# V1_0.net
KiCad netlist of a schematic drawn in Altium Designer
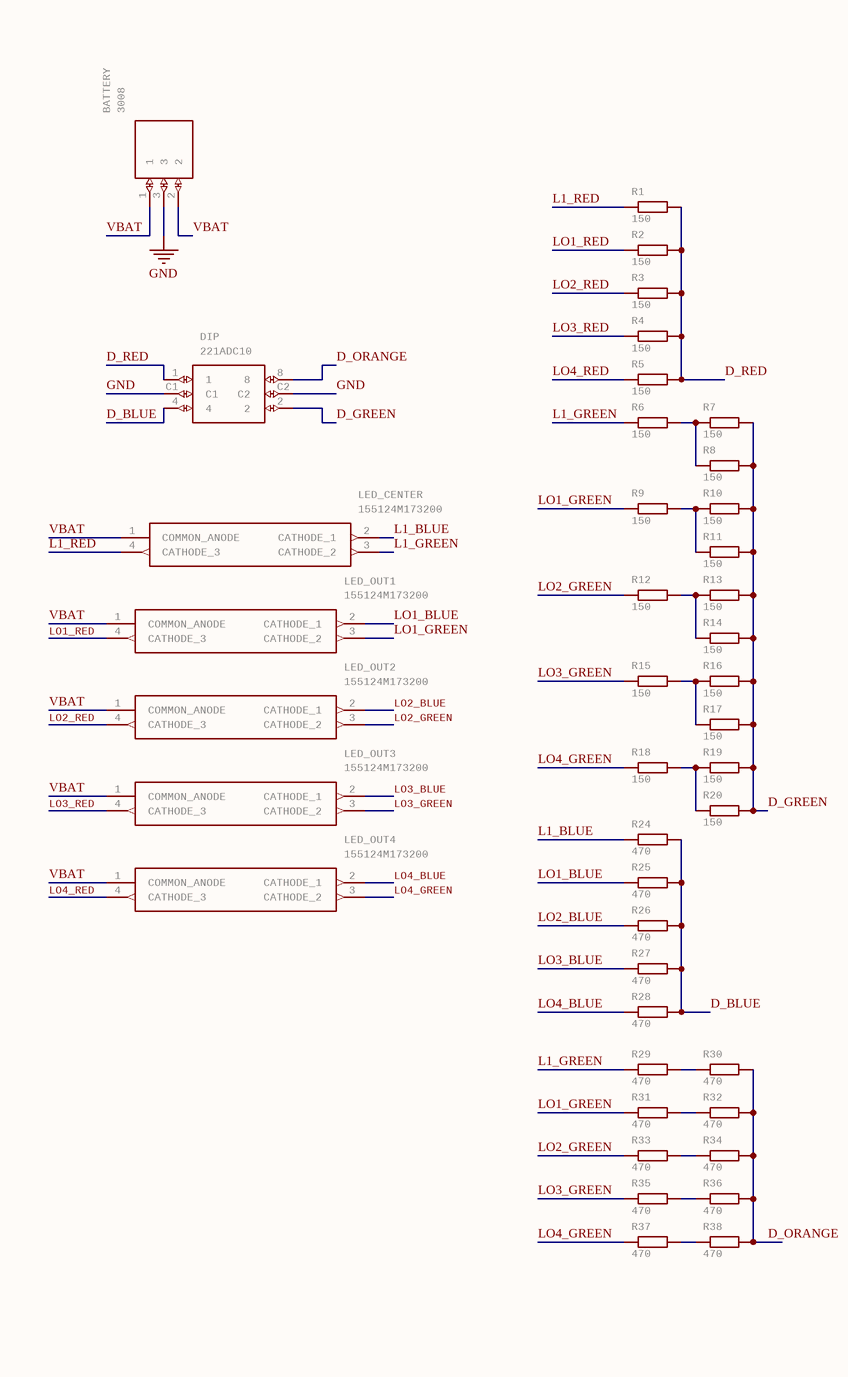
[diagram p0: V1.0.SchDoc]

(export (version "E")
  (design (tool "Eeschema 10.0.6"))
  (components
    (comp (ref "BATTERY")
      (value "3008")
      (footprint "3008")
      (description "BATTERY SOCKET   Source:  Datasheet")
      (fields (field (name "MOUSER_PART_NUMBER") "534-3008"))
      (libsource (lib "SamacSys_Parts") (part "3008"))
    )
    (comp (ref "DIP")
      (value "221ADC10")
      (footprint "221ADC10")
      (description "SWITCH ROTARY DIP BCD 100MA 50V   Source:  Datasheet")
      (fields (field (name "RS_PART_NUMBER") "1234573"))
      (libsource (lib "SamacSys_Parts") (part "221ADC10"))
    )
    (comp (ref "LED_CENTER")
      (value "155124M173200")
      (footprint "155124M173200")
      (description "WURTH ELEKTRONIK - 155124M173200 - LED, RED/GRN/BLUE, 450/850/140MCD, 1204   Source:  Datasheet")
      (fields
        (field (name "ARROW_PART_NUMBER") "ARROW_PART_NUMBER")
        (field (name "MOUSER_PART_NUMBER") "710-155124M173200")
      )
      (libsource (lib "SamacSys_Parts") (part "155124M173200"))
    )
    (comp (ref "LED_OUT1")
      (value "155124M173200")
      (footprint "155124M173200")
      (description "WURTH ELEKTRONIK - 155124M173200 - LED, RED/GRN/BLUE, 450/850/140MCD, 1204   Source:  Datasheet")
      (fields
        (field (name "ARROW_PART_NUMBER") "ARROW_PART_NUMBER")
        (field (name "MOUSER_PART_NUMBER") "710-155124M173200")
      )
      (libsource (lib "SamacSys_Parts") (part "155124M173200"))
    )
    (comp (ref "LED_OUT2")
      (value "155124M173200")
      (footprint "155124M173200")
      (description "WURTH ELEKTRONIK - 155124M173200 - LED, RED/GRN/BLUE, 450/850/140MCD, 1204   Source:  Datasheet")
      (fields
        (field (name "ARROW_PART_NUMBER") "ARROW_PART_NUMBER")
        (field (name "MOUSER_PART_NUMBER") "710-155124M173200")
      )
      (libsource (lib "SamacSys_Parts") (part "155124M173200"))
    )
    (comp (ref "LED_OUT3")
      (value "155124M173200")
      (footprint "155124M173200")
      (description "WURTH ELEKTRONIK - 155124M173200 - LED, RED/GRN/BLUE, 450/850/140MCD, 1204   Source:  Datasheet")
      (fields
        (field (name "ARROW_PART_NUMBER") "ARROW_PART_NUMBER")
        (field (name "MOUSER_PART_NUMBER") "710-155124M173200")
      )
      (libsource (lib "SamacSys_Parts") (part "155124M173200"))
    )
    (comp (ref "LED_OUT4")
      (value "155124M173200")
      (footprint "155124M173200")
      (description "WURTH ELEKTRONIK - 155124M173200 - LED, RED/GRN/BLUE, 450/850/140MCD, 1204   Source:  Datasheet")
      (fields
        (field (name "ARROW_PART_NUMBER") "ARROW_PART_NUMBER")
        (field (name "MOUSER_PART_NUMBER") "710-155124M173200")
      )
      (libsource (lib "SamacSys_Parts") (part "155124M173200"))
    )
    (comp (ref "R1")
      (value "150")
      (footprint "R0603")
      (description "RESISTOR, European symbol")
      (libsource (lib "rcl") (part "R-EU_R0603"))
    )
    (comp (ref "R2")
      (value "150")
      (footprint "R0603")
      (description "RESISTOR, European symbol")
      (libsource (lib "rcl") (part "R-EU_R0603"))
    )
    (comp (ref "R3")
      (value "150")
      (footprint "R0603")
      (description "RESISTOR, European symbol")
      (libsource (lib "rcl") (part "R-EU_R0603"))
    )
    (comp (ref "R4")
      (value "150")
      (footprint "R0603")
      (description "RESISTOR, European symbol")
      (libsource (lib "rcl") (part "R-EU_R0603"))
    )
    (comp (ref "R5")
      (value "150")
      (footprint "R0603")
      (description "RESISTOR, European symbol")
      (libsource (lib "rcl") (part "R-EU_R0603"))
    )
    (comp (ref "R6")
      (value "150")
      (footprint "R0603")
      (description "RESISTOR, European symbol")
      (libsource (lib "rcl") (part "R-EU_R0603"))
    )
    (comp (ref "R7")
      (value "150")
      (footprint "R0603")
      (description "RESISTOR, European symbol")
      (libsource (lib "rcl") (part "R-EU_R0603"))
    )
    (comp (ref "R8")
      (value "150")
      (footprint "R0603")
      (description "RESISTOR, European symbol")
      (libsource (lib "rcl") (part "R-EU_R0603"))
    )
    (comp (ref "R9")
      (value "150")
      (footprint "R0603")
      (description "RESISTOR, European symbol")
      (libsource (lib "rcl") (part "R-EU_R0603"))
    )
    (comp (ref "R10")
      (value "150")
      (footprint "R0603")
      (description "RESISTOR, European symbol")
      (libsource (lib "rcl") (part "R-EU_R0603"))
    )
    (comp (ref "R11")
      (value "150")
      (footprint "R0603")
      (description "RESISTOR, European symbol")
      (libsource (lib "rcl") (part "R-EU_R0603"))
    )
    (comp (ref "R12")
      (value "150")
      (footprint "R0603")
      (description "RESISTOR, European symbol")
      (libsource (lib "rcl") (part "R-EU_R0603"))
    )
    (comp (ref "R13")
      (value "150")
      (footprint "R0603")
      (description "RESISTOR, European symbol")
      (libsource (lib "rcl") (part "R-EU_R0603"))
    )
    (comp (ref "R14")
      (value "150")
      (footprint "R0603")
      (description "RESISTOR, European symbol")
      (libsource (lib "rcl") (part "R-EU_R0603"))
    )
    (comp (ref "R15")
      (value "150")
      (footprint "R0603")
      (description "RESISTOR, European symbol")
      (libsource (lib "rcl") (part "R-EU_R0603"))
    )
    (comp (ref "R16")
      (value "150")
      (footprint "R0603")
      (description "RESISTOR, European symbol")
      (libsource (lib "rcl") (part "R-EU_R0603"))
    )
    (comp (ref "R17")
      (value "150")
      (footprint "R0603")
      (description "RESISTOR, European symbol")
      (libsource (lib "rcl") (part "R-EU_R0603"))
    )
    (comp (ref "R18")
      (value "150")
      (footprint "R0603")
      (description "RESISTOR, European symbol")
      (libsource (lib "rcl") (part "R-EU_R0603"))
    )
    (comp (ref "R19")
      (value "150")
      (footprint "R0603")
      (description "RESISTOR, European symbol")
      (libsource (lib "rcl") (part "R-EU_R0603"))
    )
    (comp (ref "R20")
      (value "150")
      (footprint "R0603")
      (description "RESISTOR, European symbol")
      (libsource (lib "rcl") (part "R-EU_R0603"))
    )
    (comp (ref "R24")
      (value "470")
      (footprint "R0603")
      (description "RESISTOR, European symbol")
      (libsource (lib "rcl") (part "R-EU_R0603"))
    )
    (comp (ref "R25")
      (value "470")
      (footprint "R0603")
      (description "RESISTOR, European symbol")
      (libsource (lib "rcl") (part "R-EU_R0603"))
    )
    (comp (ref "R26")
      (value "470")
      (footprint "R0603")
      (description "RESISTOR, European symbol")
      (libsource (lib "rcl") (part "R-EU_R0603"))
    )
    (comp (ref "R27")
      (value "470")
      (footprint "R0603")
      (description "RESISTOR, European symbol")
      (libsource (lib "rcl") (part "R-EU_R0603"))
    )
    (comp (ref "R28")
      (value "470")
      (footprint "R0603")
      (description "RESISTOR, European symbol")
      (libsource (lib "rcl") (part "R-EU_R0603"))
    )
    (comp (ref "R29")
      (value "470")
      (footprint "R0603")
      (description "RESISTOR, European symbol")
      (libsource (lib "rcl") (part "R-EU_R0603"))
    )
    (comp (ref "R30")
      (value "470")
      (footprint "R0603")
      (description "RESISTOR, European symbol")
      (libsource (lib "rcl") (part "R-EU_R0603"))
    )
    (comp (ref "R31")
      (value "470")
      (footprint "R0603")
      (description "RESISTOR, European symbol")
      (libsource (lib "rcl") (part "R-EU_R0603"))
    )
    (comp (ref "R32")
      (value "470")
      (footprint "R0603")
      (description "RESISTOR, European symbol")
      (libsource (lib "rcl") (part "R-EU_R0603"))
    )
    (comp (ref "R33")
      (value "470")
      (footprint "R0603")
      (description "RESISTOR, European symbol")
      (libsource (lib "rcl") (part "R-EU_R0603"))
    )
    (comp (ref "R34")
      (value "470")
      (footprint "R0603")
      (description "RESISTOR, European symbol")
      (libsource (lib "rcl") (part "R-EU_R0603"))
    )
    (comp (ref "R35")
      (value "470")
      (footprint "R0603")
      (description "RESISTOR, European symbol")
      (libsource (lib "rcl") (part "R-EU_R0603"))
    )
    (comp (ref "R36")
      (value "470")
      (footprint "R0603")
      (description "RESISTOR, European symbol")
      (libsource (lib "rcl") (part "R-EU_R0603"))
    )
    (comp (ref "R37")
      (value "470")
      (footprint "R0603")
      (description "RESISTOR, European symbol")
      (libsource (lib "rcl") (part "R-EU_R0603"))
    )
    (comp (ref "R38")
      (value "470")
      (footprint "R0603")
      (description "RESISTOR, European symbol")
      (libsource (lib "rcl") (part "R-EU_R0603"))
    )
  )
  (nets
    (net (code "1") (name "/D_BLUE") (class "Default")
      (node (ref "DIP") (pin "4") (pinfunction "4_4") (pintype "bidirectional"))
      (node (ref "R24") (pin "2") (pinfunction "2_2") (pintype "passive"))
      (node (ref "R25") (pin "2") (pinfunction "2_2") (pintype "passive"))
      (node (ref "R26") (pin "2") (pinfunction "2_2") (pintype "passive"))
      (node (ref "R27") (pin "2") (pinfunction "2_2") (pintype "passive"))
      (node (ref "R28") (pin "2") (pinfunction "2_2") (pintype "passive"))
    )
    (net (code "2") (name "/D_GREEN") (class "Default")
      (node (ref "DIP") (pin "2") (pinfunction "2_2") (pintype "bidirectional"))
      (node (ref "R10") (pin "2") (pinfunction "2_2") (pintype "passive"))
      (node (ref "R11") (pin "2") (pinfunction "2_2") (pintype "passive"))
      (node (ref "R13") (pin "2") (pinfunction "2_2") (pintype "passive"))
      (node (ref "R14") (pin "2") (pinfunction "2_2") (pintype "passive"))
      (node (ref "R16") (pin "2") (pinfunction "2_2") (pintype "passive"))
      (node (ref "R17") (pin "2") (pinfunction "2_2") (pintype "passive"))
      (node (ref "R19") (pin "2") (pinfunction "2_2") (pintype "passive"))
      (node (ref "R20") (pin "2") (pinfunction "2_2") (pintype "passive"))
      (node (ref "R7") (pin "2") (pinfunction "2_2") (pintype "passive"))
      (node (ref "R8") (pin "2") (pinfunction "2_2") (pintype "passive"))
    )
    (net (code "3") (name "/D_ORANGE") (class "Default")
      (node (ref "DIP") (pin "8") (pinfunction "8_8") (pintype "bidirectional"))
      (node (ref "R30") (pin "2") (pinfunction "2_2") (pintype "passive"))
      (node (ref "R32") (pin "2") (pinfunction "2_2") (pintype "passive"))
      (node (ref "R34") (pin "2") (pinfunction "2_2") (pintype "passive"))
      (node (ref "R36") (pin "2") (pinfunction "2_2") (pintype "passive"))
      (node (ref "R38") (pin "2") (pinfunction "2_2") (pintype "passive"))
    )
    (net (code "4") (name "/D_RED") (class "Default")
      (node (ref "DIP") (pin "1") (pinfunction "1_1") (pintype "bidirectional"))
      (node (ref "R1") (pin "2") (pinfunction "2_2") (pintype "passive"))
      (node (ref "R2") (pin "2") (pinfunction "2_2") (pintype "passive"))
      (node (ref "R3") (pin "2") (pinfunction "2_2") (pintype "passive"))
      (node (ref "R4") (pin "2") (pinfunction "2_2") (pintype "passive"))
      (node (ref "R5") (pin "2") (pinfunction "2_2") (pintype "passive"))
    )
    (net (code "5") (name "/L1_BLUE") (class "Default")
      (node (ref "LED_CENTER") (pin "2") (pinfunction "CATHODE_1_2") (pintype "output"))
      (node (ref "R24") (pin "1") (pinfunction "1_1") (pintype "passive"))
    )
    (net (code "6") (name "/L1_GREEN") (class "Default")
      (node (ref "LED_CENTER") (pin "3") (pinfunction "CATHODE_2_3") (pintype "output"))
      (node (ref "R29") (pin "1") (pinfunction "1_1") (pintype "passive"))
      (node (ref "R6") (pin "1") (pinfunction "1_1") (pintype "passive"))
    )
    (net (code "7") (name "/L1_RED") (class "Default")
      (node (ref "LED_CENTER") (pin "4") (pinfunction "CATHODE_3_4") (pintype "output"))
      (node (ref "R1") (pin "1") (pinfunction "1_1") (pintype "passive"))
    )
    (net (code "8") (name "/LO1_BLUE") (class "Default")
      (node (ref "LED_OUT1") (pin "2") (pinfunction "CATHODE_1_2") (pintype "output"))
      (node (ref "R25") (pin "1") (pinfunction "1_1") (pintype "passive"))
    )
    (net (code "9") (name "/LO1_GREEN") (class "Default")
      (node (ref "LED_OUT1") (pin "3") (pinfunction "CATHODE_2_3") (pintype "output"))
      (node (ref "R31") (pin "1") (pinfunction "1_1") (pintype "passive"))
      (node (ref "R9") (pin "1") (pinfunction "1_1") (pintype "passive"))
    )
    (net (code "10") (name "/LO1_RED") (class "Default")
      (node (ref "LED_OUT1") (pin "4") (pinfunction "CATHODE_3_4") (pintype "output"))
      (node (ref "R2") (pin "1") (pinfunction "1_1") (pintype "passive"))
    )
    (net (code "11") (name "/LO2_BLUE") (class "Default")
      (node (ref "LED_OUT2") (pin "2") (pinfunction "CATHODE_1_2") (pintype "output"))
      (node (ref "R26") (pin "1") (pinfunction "1_1") (pintype "passive"))
    )
    (net (code "12") (name "/LO2_GREEN") (class "Default")
      (node (ref "LED_OUT2") (pin "3") (pinfunction "CATHODE_2_3") (pintype "output"))
      (node (ref "R12") (pin "1") (pinfunction "1_1") (pintype "passive"))
      (node (ref "R33") (pin "1") (pinfunction "1_1") (pintype "passive"))
    )
    (net (code "13") (name "/LO2_RED") (class "Default")
      (node (ref "LED_OUT2") (pin "4") (pinfunction "CATHODE_3_4") (pintype "output"))
      (node (ref "R3") (pin "1") (pinfunction "1_1") (pintype "passive"))
    )
    (net (code "14") (name "/LO3_BLUE") (class "Default")
      (node (ref "LED_OUT3") (pin "2") (pinfunction "CATHODE_1_2") (pintype "output"))
      (node (ref "R27") (pin "1") (pinfunction "1_1") (pintype "passive"))
    )
    (net (code "15") (name "/LO3_GREEN") (class "Default")
      (node (ref "LED_OUT3") (pin "3") (pinfunction "CATHODE_2_3") (pintype "output"))
      (node (ref "R15") (pin "1") (pinfunction "1_1") (pintype "passive"))
      (node (ref "R35") (pin "1") (pinfunction "1_1") (pintype "passive"))
    )
    (net (code "16") (name "/LO3_RED") (class "Default")
      (node (ref "LED_OUT3") (pin "4") (pinfunction "CATHODE_3_4") (pintype "output"))
      (node (ref "R4") (pin "1") (pinfunction "1_1") (pintype "passive"))
    )
    (net (code "17") (name "/LO4_BLUE") (class "Default")
      (node (ref "LED_OUT4") (pin "2") (pinfunction "CATHODE_1_2") (pintype "output"))
      (node (ref "R28") (pin "1") (pinfunction "1_1") (pintype "passive"))
    )
    (net (code "18") (name "/LO4_GREEN") (class "Default")
      (node (ref "LED_OUT4") (pin "3") (pinfunction "CATHODE_2_3") (pintype "output"))
      (node (ref "R18") (pin "1") (pinfunction "1_1") (pintype "passive"))
      (node (ref "R37") (pin "1") (pinfunction "1_1") (pintype "passive"))
    )
    (net (code "19") (name "/LO4_RED") (class "Default")
      (node (ref "LED_OUT4") (pin "4") (pinfunction "CATHODE_3_4") (pintype "output"))
      (node (ref "R5") (pin "1") (pinfunction "1_1") (pintype "passive"))
    )
    (net (code "20") (name "/VBAT") (class "Default")
      (node (ref "BATTERY") (pin "1") (pinfunction "1_1") (pintype "bidirectional"))
      (node (ref "BATTERY") (pin "2") (pinfunction "2_2") (pintype "bidirectional"))
      (node (ref "LED_CENTER") (pin "1") (pinfunction "COMMON_ANODE_1") (pintype "power_in"))
      (node (ref "LED_OUT1") (pin "1") (pinfunction "COMMON_ANODE_1") (pintype "power_in"))
      (node (ref "LED_OUT2") (pin "1") (pinfunction "COMMON_ANODE_1") (pintype "power_in"))
      (node (ref "LED_OUT3") (pin "1") (pinfunction "COMMON_ANODE_1") (pintype "power_in"))
      (node (ref "LED_OUT4") (pin "1") (pinfunction "COMMON_ANODE_1") (pintype "power_in"))
    )
    (net (code "21") (name "GND") (class "Default")
      (node (ref "BATTERY") (pin "3") (pinfunction "3_3") (pintype "bidirectional"))
      (node (ref "DIP") (pin "C1") (pinfunction "C1_C1") (pintype "bidirectional"))
      (node (ref "DIP") (pin "C2") (pinfunction "C2_C2") (pintype "bidirectional"))
    )
    (net (code "22") (name "Net-(R6-Pad2)") (class "Default")
      (node (ref "R6") (pin "2") (pinfunction "2_2") (pintype "passive"))
      (node (ref "R7") (pin "1") (pinfunction "1_1") (pintype "passive"))
      (node (ref "R8") (pin "1") (pinfunction "1_1") (pintype "passive"))
    )
    (net (code "23") (name "Net-(R10-Pad1)") (class "Default")
      (node (ref "R10") (pin "1") (pinfunction "1_1") (pintype "passive"))
      (node (ref "R11") (pin "1") (pinfunction "1_1") (pintype "passive"))
      (node (ref "R9") (pin "2") (pinfunction "2_2") (pintype "passive"))
    )
    (net (code "24") (name "Net-(R12-Pad2)") (class "Default")
      (node (ref "R12") (pin "2") (pinfunction "2_2") (pintype "passive"))
      (node (ref "R13") (pin "1") (pinfunction "1_1") (pintype "passive"))
      (node (ref "R14") (pin "1") (pinfunction "1_1") (pintype "passive"))
    )
    (net (code "25") (name "Net-(R15-Pad2)") (class "Default")
      (node (ref "R15") (pin "2") (pinfunction "2_2") (pintype "passive"))
      (node (ref "R16") (pin "1") (pinfunction "1_1") (pintype "passive"))
      (node (ref "R17") (pin "1") (pinfunction "1_1") (pintype "passive"))
    )
    (net (code "26") (name "Net-(R18-Pad2)") (class "Default")
      (node (ref "R18") (pin "2") (pinfunction "2_2") (pintype "passive"))
      (node (ref "R19") (pin "1") (pinfunction "1_1") (pintype "passive"))
      (node (ref "R20") (pin "1") (pinfunction "1_1") (pintype "passive"))
    )
    (net (code "27") (name "Net-(R29-Pad2)") (class "Default")
      (node (ref "R29") (pin "2") (pinfunction "2_2") (pintype "passive"))
      (node (ref "R30") (pin "1") (pinfunction "1_1") (pintype "passive"))
    )
    (net (code "28") (name "Net-(R31-Pad2)") (class "Default")
      (node (ref "R31") (pin "2") (pinfunction "2_2") (pintype "passive"))
      (node (ref "R32") (pin "1") (pinfunction "1_1") (pintype "passive"))
    )
    (net (code "29") (name "Net-(R33-Pad2)") (class "Default")
      (node (ref "R33") (pin "2") (pinfunction "2_2") (pintype "passive"))
      (node (ref "R34") (pin "1") (pinfunction "1_1") (pintype "passive"))
    )
    (net (code "30") (name "Net-(R35-Pad2)") (class "Default")
      (node (ref "R35") (pin "2") (pinfunction "2_2") (pintype "passive"))
      (node (ref "R36") (pin "1") (pinfunction "1_1") (pintype "passive"))
    )
    (net (code "31") (name "Net-(R37-Pad2)") (class "Default")
      (node (ref "R37") (pin "2") (pinfunction "2_2") (pintype "passive"))
      (node (ref "R38") (pin "1") (pinfunction "1_1") (pintype "passive"))
    )
  )
)
